# ESP_Breakout.net
KiCad netlist of a schematic drawn in EAGLE
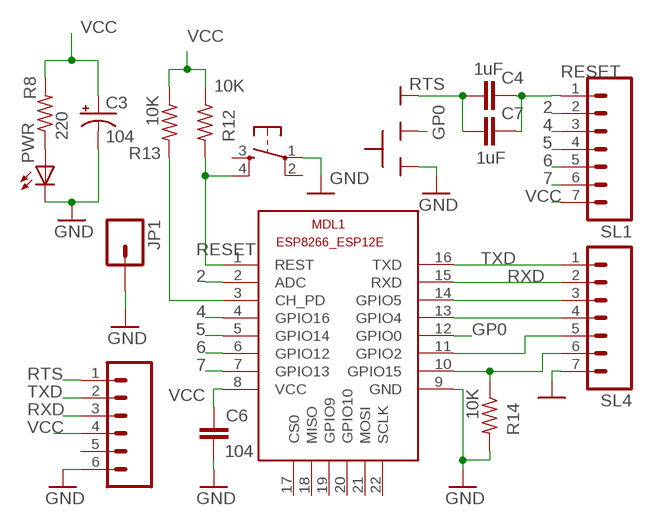
[diagram p0: schematic, sheet 1]

(export (version "E")
  (design (tool "Eeschema 10.0.6"))
  (components
    (comp (ref "C3")
      (value "104")
      (footprint "eagle-import:C_6032-28R")
      (libsource (lib "eagle-import") (part "CAP_POL_10V"))
    )
    (comp (ref "C4")
      (value "1uF")
      (footprint "eagle-import:C1206")
      (libsource (lib "eagle-import") (part "C-EUC1206"))
    )
    (comp (ref "C6")
      (value "104")
      (footprint "eagle-import:C1206")
      (libsource (lib "eagle-import") (part "C-EUC1206"))
    )
    (comp (ref "C7")
      (value "1uF")
      (footprint "eagle-import:C1206")
      (libsource (lib "eagle-import") (part "C-EUC1206"))
    )
    (comp (ref "JP1")
      (value "M01NOSILK-KIT")
      (footprint "eagle-import:1X01NS-KIT")
      (libsource (lib "eagle-import") (part "M01NOSILK-KIT"))
    )
    (comp (ref "MDL1")
      (value "ESP8266-12EESP8266-ESP12E")
      (footprint "eagle-import:ESP8266-ESP12E")
      (libsource (lib "eagle-import") (part "ESP8266-12EESP8266-ESP12E"))
    )
    (comp (ref "PWR")
      (value "LEDCHIPLED_1206")
      (footprint "eagle-import:CHIPLED_1206")
      (libsource (lib "eagle-import") (part "LEDCHIPLED_1206"))
    )
    (comp (ref "R8")
      (value "220")
      (footprint "eagle-import:R0805")
      (libsource (lib "eagle-import") (part "R-US_R0805"))
    )
    (comp (ref "R12")
      (value "10K")
      (footprint "eagle-import:R0805")
      (libsource (lib "eagle-import") (part "R-US_R0805"))
    )
    (comp (ref "R13")
      (value "10K")
      (footprint "eagle-import:R0805")
      (libsource (lib "eagle-import") (part "R-US_R0805"))
    )
    (comp (ref "R14")
      (value "10K")
      (footprint "eagle-import:R0603")
      (libsource (lib "eagle-import") (part "RESISTOR0603"))
    )
    (comp (ref "SL1")
      (value "M07")
      (footprint "eagle-import:07P")
      (libsource (lib "eagle-import") (part "M07"))
    )
    (comp (ref "SL2")
      (value "M06")
      (footprint "eagle-import:06P")
      (libsource (lib "eagle-import") (part "M06"))
    )
    (comp (ref "SL4")
      (value "M07")
      (footprint "eagle-import:07P")
      (libsource (lib "eagle-import") (part "M07"))
    )
    (comp (ref "U$1")
      (value "SLIDESWITCH-SMALL")
      (footprint "eagle-import:SMALLSWITCH")
      (libsource (lib "eagle-import") (part "SLIDESWITCH-SMALL"))
    )
    (comp (ref "U$2")
      (value "OMRON_SWITCH_10-XX")
      (footprint "eagle-import:B3F-10XX")
      (libsource (lib "eagle-import") (part "OMRON_SWITCH_10-XX"))
    )
  )
  (nets
    (net (code "1") (name "/2") (class "Default")
      (node (ref "MDL1") (pin "2") (pinfunction "ADC_2") (pintype "bidirectional"))
      (node (ref "SL1") (pin "2") (pinfunction "2_2") (pintype "passive"))
    )
    (net (code "2") (name "/4") (class "Default")
      (node (ref "MDL1") (pin "4") (pinfunction "GPIO16_4") (pintype "bidirectional"))
      (node (ref "SL1") (pin "3") (pinfunction "3_3") (pintype "passive"))
    )
    (net (code "3") (name "/5") (class "Default")
      (node (ref "MDL1") (pin "5") (pinfunction "GPIO14_5") (pintype "bidirectional"))
      (node (ref "SL1") (pin "4") (pinfunction "4_4") (pintype "passive"))
    )
    (net (code "4") (name "/6") (class "Default")
      (node (ref "MDL1") (pin "6") (pinfunction "GPIO12_6") (pintype "bidirectional"))
      (node (ref "SL1") (pin "5") (pinfunction "5_5") (pintype "passive"))
    )
    (net (code "5") (name "/7") (class "Default")
      (node (ref "MDL1") (pin "7") (pinfunction "GPIO13_7") (pintype "bidirectional"))
      (node (ref "SL1") (pin "6") (pinfunction "6_6") (pintype "passive"))
    )
    (net (code "6") (name "/GP0") (class "Default")
      (node (ref "MDL1") (pin "12") (pinfunction "GPIO0_12") (pintype "bidirectional"))
      (node (ref "U$1") (pin "2") (pinfunction "2_2") (pintype "bidirectional"))
    )
    (net (code "7") (name "/RESET") (class "Default")
      (node (ref "C4") (pin "2") (pinfunction "2_2") (pintype "passive"))
      (node (ref "C7") (pin "2") (pinfunction "2_2") (pintype "passive"))
      (node (ref "MDL1") (pin "1") (pinfunction "REST_1") (pintype "bidirectional"))
      (node (ref "R12") (pin "2") (pinfunction "2_2") (pintype "passive"))
      (node (ref "SL1") (pin "1") (pinfunction "1_1") (pintype "passive"))
      (node (ref "U$2") (pin "4") (pinfunction "S1_4") (pintype "passive"))
    )
    (net (code "8") (name "/RTS") (class "Default")
      (node (ref "C4") (pin "1") (pinfunction "1_1") (pintype "passive"))
      (node (ref "C7") (pin "1") (pinfunction "1_1") (pintype "passive"))
      (node (ref "SL2") (pin "1") (pinfunction "1_1") (pintype "passive"))
      (node (ref "U$1") (pin "3") (pinfunction "3_3") (pintype "bidirectional"))
    )
    (net (code "9") (name "/RXD") (class "Default")
      (node (ref "MDL1") (pin "15") (pinfunction "RXD_15") (pintype "bidirectional"))
      (node (ref "SL2") (pin "3") (pinfunction "3_3") (pintype "passive"))
      (node (ref "SL4") (pin "2") (pinfunction "2_2") (pintype "passive"))
    )
    (net (code "10") (name "/TXD") (class "Default")
      (node (ref "MDL1") (pin "16") (pinfunction "TXD_16") (pintype "bidirectional"))
      (node (ref "SL2") (pin "2") (pinfunction "2_2") (pintype "passive"))
      (node (ref "SL4") (pin "1") (pinfunction "1_1") (pintype "passive"))
    )
    (net (code "11") (name "/VCC") (class "Default")
      (node (ref "C3") (pin "+") (pinfunction "+_+") (pintype "passive"))
      (node (ref "C6") (pin "1") (pinfunction "1_1") (pintype "passive"))
      (node (ref "MDL1") (pin "8") (pinfunction "VCC_8") (pintype "bidirectional"))
      (node (ref "R12") (pin "1") (pinfunction "1_1") (pintype "passive"))
      (node (ref "R13") (pin "1") (pinfunction "1_1") (pintype "passive"))
      (node (ref "R8") (pin "2") (pinfunction "2_2") (pintype "passive"))
      (node (ref "SL1") (pin "7") (pinfunction "7_7") (pintype "passive"))
      (node (ref "SL2") (pin "4") (pinfunction "4_4") (pintype "passive"))
    )
    (net (code "12") (name "GND") (class "Default")
      (node (ref "C3") (pin "-") (pinfunction "-_-") (pintype "passive"))
      (node (ref "C6") (pin "2") (pinfunction "2_2") (pintype "passive"))
      (node (ref "JP1") (pin "1") (pinfunction "1_1") (pintype "passive"))
      (node (ref "MDL1") (pin "9") (pinfunction "GND_9") (pintype "bidirectional"))
      (node (ref "PWR") (pin "C") (pinfunction "C_C") (pintype "passive"))
      (node (ref "R14") (pin "2") (pinfunction "2_2") (pintype "passive"))
      (node (ref "SL2") (pin "6") (pinfunction "6_6") (pintype "passive"))
      (node (ref "SL4") (pin "7") (pinfunction "7_7") (pintype "passive"))
      (node (ref "U$1") (pin "1") (pinfunction "1_1") (pintype "bidirectional"))
      (node (ref "U$2") (pin "1") (pinfunction "P_1") (pintype "passive"))
    )
    (net (code "13") (name "Net-(MDL1-CH_PD)") (class "Default")
      (node (ref "MDL1") (pin "3") (pinfunction "CH_PD_3") (pintype "bidirectional"))
      (node (ref "R13") (pin "2") (pinfunction "2_2") (pintype "passive"))
    )
    (net (code "14") (name "Net-(MDL1-GPIO2)") (class "Default")
      (node (ref "MDL1") (pin "11") (pinfunction "GPIO2_11") (pintype "bidirectional"))
      (node (ref "SL4") (pin "5") (pinfunction "5_5") (pintype "passive"))
    )
    (net (code "15") (name "Net-(MDL1-GPIO4)") (class "Default")
      (node (ref "MDL1") (pin "13") (pinfunction "GPIO4_13") (pintype "bidirectional"))
      (node (ref "SL4") (pin "4") (pinfunction "4_4") (pintype "passive"))
    )
    (net (code "16") (name "Net-(MDL1-GPIO5)") (class "Default")
      (node (ref "MDL1") (pin "14") (pinfunction "GPIO5_14") (pintype "bidirectional"))
      (node (ref "SL4") (pin "3") (pinfunction "3_3") (pintype "passive"))
    )
    (net (code "17") (name "Net-(MDL1-GPIO15)") (class "Default")
      (node (ref "MDL1") (pin "10") (pinfunction "GPIO15_10") (pintype "bidirectional"))
      (node (ref "R14") (pin "1") (pinfunction "1_1") (pintype "passive"))
      (node (ref "SL4") (pin "6") (pinfunction "6_6") (pintype "passive"))
    )
    (net (code "18") (name "Net-(PWR-PadA)") (class "Default")
      (node (ref "PWR") (pin "A") (pinfunction "A_A") (pintype "passive"))
      (node (ref "R8") (pin "1") (pinfunction "1_1") (pintype "passive"))
    )
    (net (code "19") (name "unconnected-(MDL1-CS0-Pad17)") (class "Default")
      (node (ref "MDL1") (pin "17") (pinfunction "CS0_17") (pintype "bidirectional"))
    )
    (net (code "20") (name "unconnected-(MDL1-GPIO9-Pad19)") (class "Default")
      (node (ref "MDL1") (pin "19") (pinfunction "GPIO9_19") (pintype "bidirectional"))
    )
    (net (code "21") (name "unconnected-(MDL1-GPIO10-Pad20)") (class "Default")
      (node (ref "MDL1") (pin "20") (pinfunction "GPIO10_20") (pintype "bidirectional"))
    )
    (net (code "22") (name "unconnected-(MDL1-MISO-Pad18)") (class "Default")
      (node (ref "MDL1") (pin "18") (pinfunction "MISO_18") (pintype "bidirectional"))
    )
    (net (code "23") (name "unconnected-(MDL1-MOSI-Pad21)") (class "Default")
      (node (ref "MDL1") (pin "21") (pinfunction "MOSI_21") (pintype "bidirectional"))
    )
    (net (code "24") (name "unconnected-(MDL1-SCLK-Pad22)") (class "Default")
      (node (ref "MDL1") (pin "22") (pinfunction "SCLK_22") (pintype "bidirectional"))
    )
    (net (code "25") (name "unconnected-(SL2-Pad5)") (class "Default")
      (node (ref "SL2") (pin "5") (pinfunction "5_5") (pintype "passive"))
    )
    (net (code "26") (name "unconnected-(U$2-P1-Pad2)") (class "Default")
      (node (ref "U$2") (pin "2") (pinfunction "P1_2") (pintype "passive"))
    )
    (net (code "27") (name "unconnected-(U$2-S-Pad3)") (class "Default")
      (node (ref "U$2") (pin "3") (pinfunction "S_3") (pintype "passive"))
    )
  )
)
